# cerebro.net
KiCad netlist of a schematic drawn in EAGLE
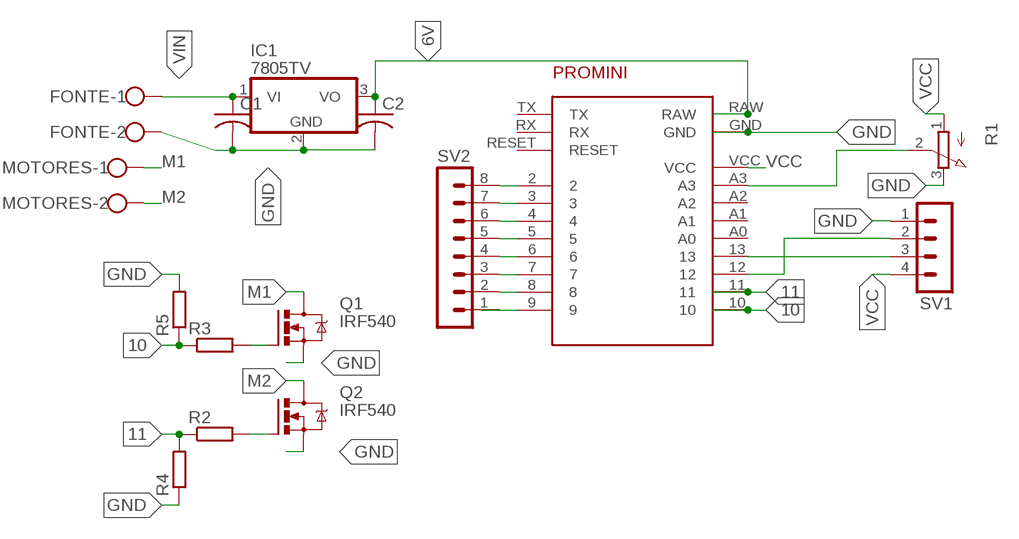
[diagram p0: schematic, sheet 1]

(export (version "E")
  (design (tool "Eeschema 10.0.6"))
  (components
    (comp (ref "C1")
      (value "C-US025-024X044")
      (footprint "eagle-import:C025-024X044")
      (libsource (lib "eagle-import") (part "C-US025-024X044"))
    )
    (comp (ref "C2")
      (value "C-US025-024X044")
      (footprint "eagle-import:C025-024X044")
      (libsource (lib "eagle-import") (part "C-US025-024X044"))
    )
    (comp (ref "FONTE")
      (value "W237-102")
      (footprint "eagle-import:W237-102")
      (fields (field (name "MPN") "237-102"))
      (libsource (lib "eagle-import") (part "W237-102"))
    )
    (comp (ref "IC1")
      (value "7805TV")
      (footprint "eagle-import:TO220V")
      (libsource (lib "eagle-import") (part "78TV05"))
    )
    (comp (ref "MOTORES")
      (value "W237-102")
      (footprint "eagle-import:W237-102")
      (fields (field (name "MPN") "237-102"))
      (libsource (lib "eagle-import") (part "W237-102"))
    )
    (comp (ref "Q1")
      (value "IRF540")
      (footprint "eagle-import:TO220BV")
      (libsource (lib "eagle-import") (part "IRF540"))
    )
    (comp (ref "Q2")
      (value "IRF540")
      (footprint "eagle-import:TO220BV")
      (libsource (lib "eagle-import") (part "IRF540"))
    )
    (comp (ref "R1")
      (value "3RP/1610N")
      (footprint "eagle-import:3RP_1610N")
      (libsource (lib "eagle-import") (part "3RP/1610N"))
    )
    (comp (ref "R2")
      (value "R-EU_0207/10")
      (footprint "eagle-import:0207_10")
      (libsource (lib "eagle-import") (part "R-EU_0207/10"))
    )
    (comp (ref "R3")
      (value "R-EU_0207/10")
      (footprint "eagle-import:0207_10")
      (libsource (lib "eagle-import") (part "R-EU_0207/10"))
    )
    (comp (ref "R4")
      (value "R-EU_0207/10")
      (footprint "eagle-import:0207_10")
      (libsource (lib "eagle-import") (part "R-EU_0207/10"))
    )
    (comp (ref "R5")
      (value "R-EU_0207/10")
      (footprint "eagle-import:0207_10")
      (libsource (lib "eagle-import") (part "R-EU_0207/10"))
    )
    (comp (ref "SV1")
      (value "MA04-1")
      (footprint "eagle-import:MA04-1")
      (libsource (lib "eagle-import") (part "MA04-1"))
    )
    (comp (ref "SV2")
      (value "MA08-1")
      (footprint "eagle-import:MA08-1")
      (libsource (lib "eagle-import") (part "MA08-1"))
    )
    (comp (ref "U$1")
      (value "PROMINI")
      (footprint "eagle-import:MICROCONTROLADOR")
      (libsource (lib "eagle-import") (part "PROMINI"))
    )
  )
  (nets
    (net (code "1") (name "6V") (class "Default")
      (node (ref "C2") (pin "1") (pinfunction "1_1") (pintype "passive"))
      (node (ref "IC1") (pin "3") (pinfunction "VO_3") (pintype "passive"))
      (node (ref "U$1") (pin "RAW") (pinfunction "RAW_RAW") (pintype "bidirectional"))
    )
    (net (code "2") (name "10") (class "Default")
      (node (ref "R3") (pin "1") (pinfunction "1_1") (pintype "passive"))
      (node (ref "R5") (pin "1") (pinfunction "1_1") (pintype "passive"))
      (node (ref "U$1") (pin "10") (pinfunction "10_10") (pintype "bidirectional"))
    )
    (net (code "3") (name "11") (class "Default")
      (node (ref "R2") (pin "1") (pinfunction "1_1") (pintype "passive"))
      (node (ref "R4") (pin "2") (pinfunction "2_2") (pintype "passive"))
      (node (ref "U$1") (pin "11") (pinfunction "11_11") (pintype "bidirectional"))
    )
    (net (code "4") (name "GND") (class "Default")
      (node (ref "C1") (pin "2") (pinfunction "2_2") (pintype "passive"))
      (node (ref "C2") (pin "2") (pinfunction "2_2") (pintype "passive"))
      (node (ref "FONTE") (pin "2") (pinfunction "KL_2") (pintype "passive"))
      (node (ref "IC1") (pin "2") (pinfunction "GND_2") (pintype "passive"))
      (node (ref "Q1") (pin "S") (pinfunction "S_S") (pintype "passive"))
      (node (ref "Q2") (pin "S") (pinfunction "S_S") (pintype "passive"))
      (node (ref "R1") (pin "3") (pinfunction "E_3") (pintype "passive"))
      (node (ref "R4") (pin "1") (pinfunction "1_1") (pintype "passive"))
      (node (ref "R5") (pin "2") (pinfunction "2_2") (pintype "passive"))
      (node (ref "SV1") (pin "1") (pinfunction "1_1") (pintype "passive"))
      (node (ref "U$1") (pin "GND") (pinfunction "GND_GND") (pintype "bidirectional"))
    )
    (net (code "5") (name "M1") (class "Default")
      (node (ref "MOTORES") (pin "1") (pinfunction "KL_1") (pintype "passive"))
      (node (ref "Q1") (pin "D") (pinfunction "D_D") (pintype "passive"))
    )
    (net (code "6") (name "M2") (class "Default")
      (node (ref "MOTORES") (pin "2") (pinfunction "KL_2") (pintype "passive"))
      (node (ref "Q2") (pin "D") (pinfunction "D_D") (pintype "passive"))
    )
    (net (code "7") (name "Net-(Q1-PadG)") (class "Default")
      (node (ref "Q1") (pin "G") (pinfunction "G_G") (pintype "passive"))
      (node (ref "R3") (pin "2") (pinfunction "2_2") (pintype "passive"))
    )
    (net (code "8") (name "Net-(Q2-PadG)") (class "Default")
      (node (ref "Q2") (pin "G") (pinfunction "G_G") (pintype "passive"))
      (node (ref "R2") (pin "2") (pinfunction "2_2") (pintype "passive"))
    )
    (net (code "9") (name "Net-(R1-S)") (class "Default")
      (node (ref "R1") (pin "2") (pinfunction "S_2") (pintype "passive"))
      (node (ref "U$1") (pin "A3") (pinfunction "A3_A3") (pintype "bidirectional"))
    )
    (net (code "10") (name "Net-(SV1-Pad2)") (class "Default")
      (node (ref "SV1") (pin "2") (pinfunction "2_2") (pintype "passive"))
      (node (ref "U$1") (pin "12") (pinfunction "12_12") (pintype "bidirectional"))
    )
    (net (code "11") (name "Net-(SV1-Pad3)") (class "Default")
      (node (ref "SV1") (pin "3") (pinfunction "3_3") (pintype "passive"))
      (node (ref "U$1") (pin "13") (pinfunction "13_13") (pintype "bidirectional"))
    )
    (net (code "12") (name "Net-(SV2-Pad2)") (class "Default")
      (node (ref "SV2") (pin "2") (pinfunction "2_2") (pintype "passive"))
      (node (ref "U$1") (pin "8") (pinfunction "8_8") (pintype "bidirectional"))
    )
    (net (code "13") (name "Net-(SV2-Pad3)") (class "Default")
      (node (ref "SV2") (pin "3") (pinfunction "3_3") (pintype "passive"))
      (node (ref "U$1") (pin "7") (pinfunction "7_7") (pintype "bidirectional"))
    )
    (net (code "14") (name "Net-(SV2-Pad4)") (class "Default")
      (node (ref "SV2") (pin "4") (pinfunction "4_4") (pintype "passive"))
      (node (ref "U$1") (pin "6") (pinfunction "6_6") (pintype "bidirectional"))
    )
    (net (code "15") (name "Net-(SV2-Pad5)") (class "Default")
      (node (ref "SV2") (pin "5") (pinfunction "5_5") (pintype "passive"))
      (node (ref "U$1") (pin "5") (pinfunction "5_5") (pintype "bidirectional"))
    )
    (net (code "16") (name "Net-(SV2-Pad6)") (class "Default")
      (node (ref "SV2") (pin "6") (pinfunction "6_6") (pintype "passive"))
      (node (ref "U$1") (pin "4") (pinfunction "4_4") (pintype "bidirectional"))
    )
    (net (code "17") (name "Net-(SV2-Pad7)") (class "Default")
      (node (ref "SV2") (pin "7") (pinfunction "7_7") (pintype "passive"))
      (node (ref "U$1") (pin "3") (pinfunction "3_3") (pintype "bidirectional"))
    )
    (net (code "18") (name "Net-(SV2-Pad8)") (class "Default")
      (node (ref "SV2") (pin "8") (pinfunction "8_8") (pintype "passive"))
      (node (ref "U$1") (pin "2") (pinfunction "2_2") (pintype "bidirectional"))
    )
    (net (code "19") (name "VCC") (class "Default")
      (node (ref "R1") (pin "1") (pinfunction "A_1") (pintype "passive"))
      (node (ref "SV1") (pin "4") (pinfunction "4_4") (pintype "passive"))
      (node (ref "U$1") (pin "VCC") (pinfunction "VCC_VCC") (pintype "bidirectional"))
    )
    (net (code "20") (name "VIN") (class "Default")
      (node (ref "C1") (pin "1") (pinfunction "1_1") (pintype "passive"))
      (node (ref "FONTE") (pin "1") (pinfunction "KL_1") (pintype "passive"))
      (node (ref "IC1") (pin "1") (pinfunction "VI_1") (pintype "input"))
    )
    (net (code "21") (name "unconnected-(SV2-Pad1)") (class "Default")
      (node (ref "SV2") (pin "1") (pinfunction "1_1") (pintype "passive"))
    )
    (net (code "22") (name "unconnected-(U$1-Pad9)") (class "Default")
      (node (ref "U$1") (pin "9") (pinfunction "9_9") (pintype "bidirectional"))
    )
    (net (code "23") (name "unconnected-(U$1-PadA0)") (class "Default")
      (node (ref "U$1") (pin "A0") (pinfunction "A0_A0") (pintype "bidirectional"))
    )
    (net (code "24") (name "unconnected-(U$1-PadA1)") (class "Default")
      (node (ref "U$1") (pin "A1") (pinfunction "A1_A1") (pintype "bidirectional"))
    )
    (net (code "25") (name "unconnected-(U$1-PadA2)") (class "Default")
      (node (ref "U$1") (pin "A2") (pinfunction "A2_A2") (pintype "bidirectional"))
    )
    (net (code "26") (name "unconnected-(U$1-PadRESET)") (class "Default")
      (node (ref "U$1") (pin "RESET") (pinfunction "RESET_RESET") (pintype "bidirectional"))
    )
    (net (code "27") (name "unconnected-(U$1-PadRX)") (class "Default")
      (node (ref "U$1") (pin "RX") (pinfunction "RX_RX") (pintype "bidirectional"))
    )
    (net (code "28") (name "unconnected-(U$1-PadTX)") (class "Default")
      (node (ref "U$1") (pin "TX") (pinfunction "TX_TX") (pintype "bidirectional"))
    )
  )
)
